# Sheet1.net
KiCad netlist of a schematic drawn in Altium Designer
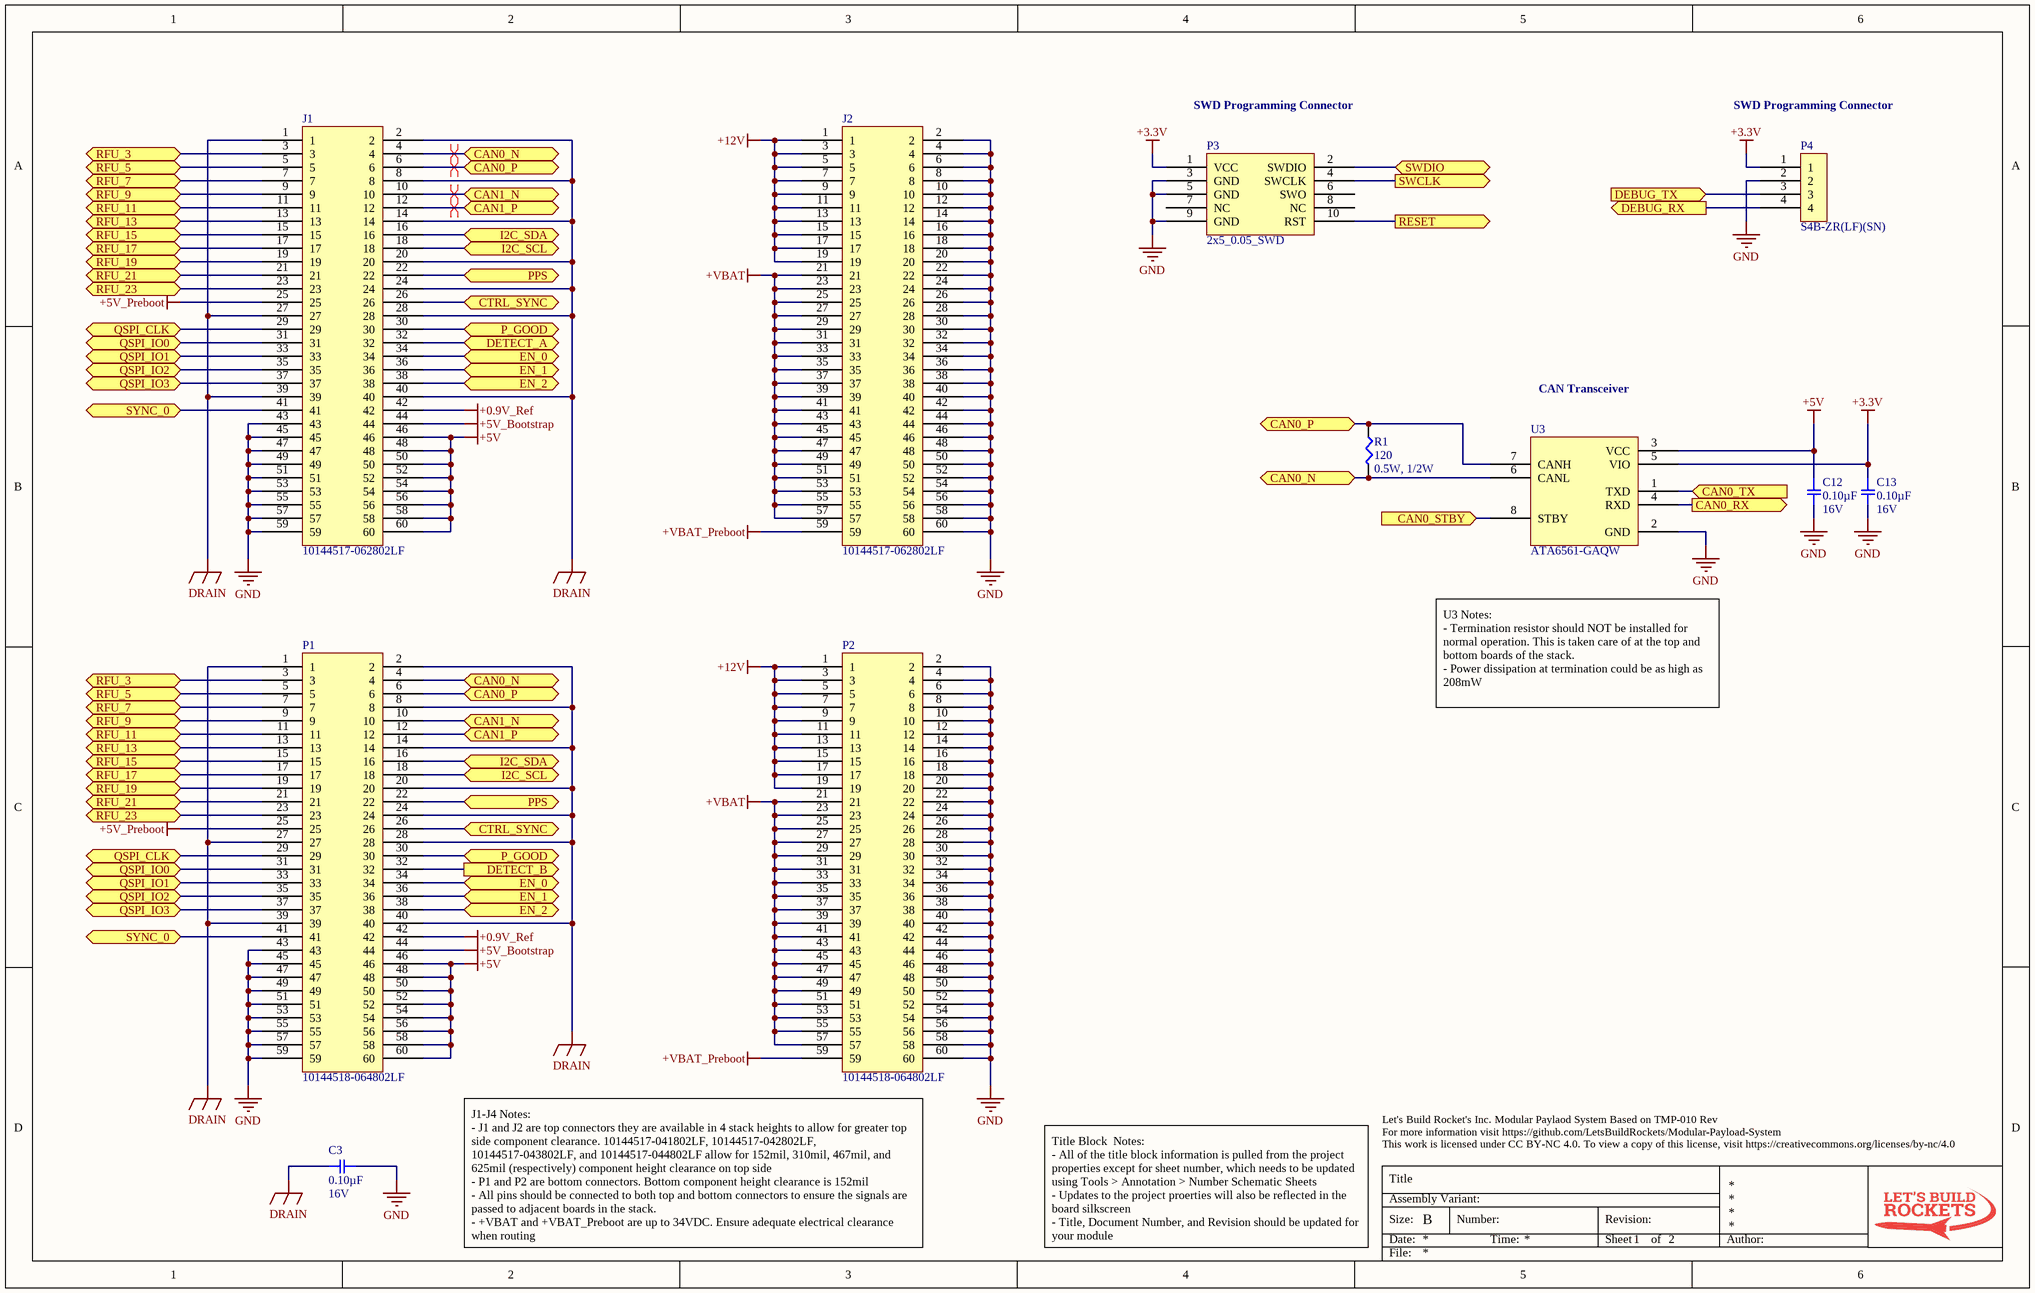
[diagram p0: Sheet1.SchDoc]

(export (version "E")
  (design (tool "Eeschema 10.0.6"))
  (components
    (comp (ref "C3")
      (value "0.10µF")
      (footprint "SMD-0402C")
      (description "CAP CER 0.1UF 16V X7R 0402")
      (fields
        (field (name "DIGI-KEY PART NUMBER") "490-4759-1-ND")
        (field (name "PART NUMBER") "GCM155R71C104KA55D")
        (field (name "VOLTAGE") "16V")
      )
      (libsource (lib "capacitor_murata_0402") (part "GCM155R71C104KA55D"))
    )
    (comp (ref "C12")
      (value "0.10µF")
      (footprint "SMD-0402C")
      (description "CAP CER 0.1UF 16V X7R 0402")
      (fields
        (field (name "DIGI-KEY PART NUMBER") "490-4759-1-ND")
        (field (name "PART NUMBER") "GCM155R71C104KA55D")
        (field (name "VOLTAGE") "16V")
      )
      (libsource (lib "capacitor_murata_0402") (part "GCM155R71C104KA55D"))
    )
    (comp (ref "C13")
      (value "0.10µF")
      (footprint "SMD-0402C")
      (description "CAP CER 0.1UF 16V X7R 0402")
      (fields
        (field (name "DIGI-KEY PART NUMBER") "490-4759-1-ND")
        (field (name "PART NUMBER") "GCM155R71C104KA55D")
        (field (name "VOLTAGE") "16V")
      )
      (libsource (lib "capacitor_murata_0402") (part "GCM155R71C104KA55D"))
    )
    (comp (ref "J1")
      (value "10144517-062802LF")
      (footprint "10144517-062802LF")
      (libsource (lib "ModularPayload") (part "10144517-062802LF"))
    )
    (comp (ref "J2")
      (value "10144517-062802LF")
      (footprint "10144517-062802LF")
      (libsource (lib "ModularPayload") (part "10144517-062802LF"))
    )
    (comp (ref "P1")
      (value "10144518-064802LF")
      (footprint "10144518-064802LF")
      (libsource (lib "ModularPayload") (part "10144518-064802LF"))
    )
    (comp (ref "P2")
      (value "10144518-064802LF")
      (footprint "10144518-064802LF")
      (libsource (lib "ModularPayload") (part "10144518-064802LF"))
    )
    (comp (ref "P3")
      (value "2x5_0.05_SWD")
      (footprint "2x5_0.05_R")
      (libsource (lib "ModularPayload") (part "2x5_0.05_SWD"))
    )
    (comp (ref "P4")
      (value "S4B-ZR(LF)(SN)")
      (footprint "S4B-ZR(LF)(SN)")
      (libsource (lib "ModularPayload") (part "S4B-ZR(LF)(SN)"))
    )
    (comp (ref "R1")
      (value "120")
      (footprint "SMD-0805-RES")
      (description "RES SMD 120 OHM 5% 1/2W 0805")
      (fields
        (field (name "PART NUMBER") "ERJ-P6WJ121V")
        (field (name "DIGI-KEY PART NUMBER") "P16943CT-ND")
        (field (name "POWER (WATTS)") "0.5W, 1/2W")
      )
      (libsource (lib "Panasonic_ERJ_0805") (part "ERJ-P6WJ121V"))
    )
    (comp (ref "U3")
      (value "ATA6561-GAQW")
      (footprint "SOIC127P600X175-8N")
      (libsource (lib "ModularPayload") (part "ATA6561-GAQW"))
    )
  )
  (nets
    (net (code "1") (name "+0.9V_Ref") (class "Default")
      (node (ref "J1") (pin "42") (pinfunction "42_42") (pintype "passive"))
      (node (ref "P1") (pin "42") (pinfunction "42_42") (pintype "passive"))
    )
    (net (code "2") (name "+3.3V") (class "Default")
      (node (ref "C13") (pin "1") (pinfunction "1_1") (pintype "passive"))
      (node (ref "P3") (pin "1") (pinfunction "VCC_1") (pintype "passive"))
      (node (ref "P4") (pin "1") (pinfunction "1_1") (pintype "passive"))
      (node (ref "U3") (pin "5") (pinfunction "VIO_5") (pintype "passive"))
    )
    (net (code "3") (name "+5V") (class "Default")
      (node (ref "C12") (pin "1") (pinfunction "1_1") (pintype "passive"))
      (node (ref "J1") (pin "46") (pinfunction "46_46") (pintype "passive"))
      (node (ref "J1") (pin "48") (pinfunction "48_48") (pintype "passive"))
      (node (ref "J1") (pin "50") (pinfunction "50_50") (pintype "passive"))
      (node (ref "J1") (pin "52") (pinfunction "52_52") (pintype "passive"))
      (node (ref "J1") (pin "54") (pinfunction "54_54") (pintype "passive"))
      (node (ref "J1") (pin "56") (pinfunction "56_56") (pintype "passive"))
      (node (ref "J1") (pin "58") (pinfunction "58_58") (pintype "passive"))
      (node (ref "J1") (pin "60") (pinfunction "60_60") (pintype "passive"))
      (node (ref "P1") (pin "46") (pinfunction "46_46") (pintype "passive"))
      (node (ref "P1") (pin "48") (pinfunction "48_48") (pintype "passive"))
      (node (ref "P1") (pin "50") (pinfunction "50_50") (pintype "passive"))
      (node (ref "P1") (pin "52") (pinfunction "52_52") (pintype "passive"))
      (node (ref "P1") (pin "54") (pinfunction "54_54") (pintype "passive"))
      (node (ref "P1") (pin "56") (pinfunction "56_56") (pintype "passive"))
      (node (ref "P1") (pin "58") (pinfunction "58_58") (pintype "passive"))
      (node (ref "P1") (pin "60") (pinfunction "60_60") (pintype "passive"))
      (node (ref "U3") (pin "3") (pinfunction "VCC_3") (pintype "passive"))
    )
    (net (code "4") (name "+5V_Bootstrap") (class "Default")
      (node (ref "J1") (pin "44") (pinfunction "44_44") (pintype "passive"))
      (node (ref "P1") (pin "44") (pinfunction "44_44") (pintype "passive"))
    )
    (net (code "5") (name "+5V_Preboot") (class "Default")
      (node (ref "J1") (pin "25") (pinfunction "25_25") (pintype "passive"))
      (node (ref "P1") (pin "25") (pinfunction "25_25") (pintype "passive"))
    )
    (net (code "6") (name "+12V") (class "Default")
      (node (ref "J2") (pin "1") (pinfunction "1_1") (pintype "passive"))
      (node (ref "J2") (pin "11") (pinfunction "11_11") (pintype "passive"))
      (node (ref "J2") (pin "13") (pinfunction "13_13") (pintype "passive"))
      (node (ref "J2") (pin "15") (pinfunction "15_15") (pintype "passive"))
      (node (ref "J2") (pin "17") (pinfunction "17_17") (pintype "passive"))
      (node (ref "J2") (pin "19") (pinfunction "19_19") (pintype "passive"))
      (node (ref "J2") (pin "3") (pinfunction "3_3") (pintype "passive"))
      (node (ref "J2") (pin "5") (pinfunction "5_5") (pintype "passive"))
      (node (ref "J2") (pin "7") (pinfunction "7_7") (pintype "passive"))
      (node (ref "J2") (pin "9") (pinfunction "9_9") (pintype "passive"))
      (node (ref "P2") (pin "1") (pinfunction "1_1") (pintype "passive"))
      (node (ref "P2") (pin "11") (pinfunction "11_11") (pintype "passive"))
      (node (ref "P2") (pin "13") (pinfunction "13_13") (pintype "passive"))
      (node (ref "P2") (pin "15") (pinfunction "15_15") (pintype "passive"))
      (node (ref "P2") (pin "17") (pinfunction "17_17") (pintype "passive"))
      (node (ref "P2") (pin "19") (pinfunction "19_19") (pintype "passive"))
      (node (ref "P2") (pin "3") (pinfunction "3_3") (pintype "passive"))
      (node (ref "P2") (pin "5") (pinfunction "5_5") (pintype "passive"))
      (node (ref "P2") (pin "7") (pinfunction "7_7") (pintype "passive"))
      (node (ref "P2") (pin "9") (pinfunction "9_9") (pintype "passive"))
    )
    (net (code "7") (name "+VBAT") (class "Default")
      (node (ref "J2") (pin "21") (pinfunction "21_21") (pintype "passive"))
      (node (ref "J2") (pin "23") (pinfunction "23_23") (pintype "passive"))
      (node (ref "J2") (pin "25") (pinfunction "25_25") (pintype "passive"))
      (node (ref "J2") (pin "27") (pinfunction "27_27") (pintype "passive"))
      (node (ref "J2") (pin "29") (pinfunction "29_29") (pintype "passive"))
      (node (ref "J2") (pin "31") (pinfunction "31_31") (pintype "passive"))
      (node (ref "J2") (pin "33") (pinfunction "33_33") (pintype "passive"))
      (node (ref "J2") (pin "35") (pinfunction "35_35") (pintype "passive"))
      (node (ref "J2") (pin "37") (pinfunction "37_37") (pintype "passive"))
      (node (ref "J2") (pin "39") (pinfunction "39_39") (pintype "passive"))
      (node (ref "J2") (pin "41") (pinfunction "41_41") (pintype "passive"))
      (node (ref "J2") (pin "43") (pinfunction "43_43") (pintype "passive"))
      (node (ref "J2") (pin "45") (pinfunction "45_45") (pintype "passive"))
      (node (ref "J2") (pin "47") (pinfunction "47_47") (pintype "passive"))
      (node (ref "J2") (pin "49") (pinfunction "49_49") (pintype "passive"))
      (node (ref "J2") (pin "51") (pinfunction "51_51") (pintype "passive"))
      (node (ref "J2") (pin "53") (pinfunction "53_53") (pintype "passive"))
      (node (ref "J2") (pin "55") (pinfunction "55_55") (pintype "passive"))
      (node (ref "J2") (pin "57") (pinfunction "57_57") (pintype "passive"))
      (node (ref "P2") (pin "21") (pinfunction "21_21") (pintype "passive"))
      (node (ref "P2") (pin "23") (pinfunction "23_23") (pintype "passive"))
      (node (ref "P2") (pin "25") (pinfunction "25_25") (pintype "passive"))
      (node (ref "P2") (pin "27") (pinfunction "27_27") (pintype "passive"))
      (node (ref "P2") (pin "29") (pinfunction "29_29") (pintype "passive"))
      (node (ref "P2") (pin "31") (pinfunction "31_31") (pintype "passive"))
      (node (ref "P2") (pin "33") (pinfunction "33_33") (pintype "passive"))
      (node (ref "P2") (pin "35") (pinfunction "35_35") (pintype "passive"))
      (node (ref "P2") (pin "37") (pinfunction "37_37") (pintype "passive"))
      (node (ref "P2") (pin "39") (pinfunction "39_39") (pintype "passive"))
      (node (ref "P2") (pin "41") (pinfunction "41_41") (pintype "passive"))
      (node (ref "P2") (pin "43") (pinfunction "43_43") (pintype "passive"))
      (node (ref "P2") (pin "45") (pinfunction "45_45") (pintype "passive"))
      (node (ref "P2") (pin "47") (pinfunction "47_47") (pintype "passive"))
      (node (ref "P2") (pin "49") (pinfunction "49_49") (pintype "passive"))
      (node (ref "P2") (pin "51") (pinfunction "51_51") (pintype "passive"))
      (node (ref "P2") (pin "53") (pinfunction "53_53") (pintype "passive"))
      (node (ref "P2") (pin "55") (pinfunction "55_55") (pintype "passive"))
      (node (ref "P2") (pin "57") (pinfunction "57_57") (pintype "passive"))
    )
    (net (code "8") (name "+VBAT_Preboot") (class "Default")
      (node (ref "J2") (pin "59") (pinfunction "59_59") (pintype "passive"))
      (node (ref "P2") (pin "59") (pinfunction "59_59") (pintype "passive"))
    )
    (net (code "9") (name "/CAN0_N") (class "Default")
      (node (ref "J1") (pin "4") (pinfunction "4_4") (pintype "passive"))
      (node (ref "P1") (pin "4") (pinfunction "4_4") (pintype "passive"))
      (node (ref "R1") (pin "2") (pinfunction "2_2") (pintype "passive"))
      (node (ref "U3") (pin "6") (pinfunction "CANL_6") (pintype "passive"))
    )
    (net (code "10") (name "/CAN0_P") (class "Default")
      (node (ref "J1") (pin "6") (pinfunction "6_6") (pintype "passive"))
      (node (ref "P1") (pin "6") (pinfunction "6_6") (pintype "passive"))
      (node (ref "R1") (pin "1") (pinfunction "1_1") (pintype "passive"))
      (node (ref "U3") (pin "7") (pinfunction "CANH_7") (pintype "passive"))
    )
    (net (code "11") (name "/CAN0_RX") (class "Default")
      (node (ref "U3") (pin "4") (pinfunction "RXD_4") (pintype "passive"))
    )
    (net (code "12") (name "/CAN0_STBY") (class "Default")
      (node (ref "U3") (pin "8") (pinfunction "STBY_8") (pintype "passive"))
    )
    (net (code "13") (name "/CAN0_TX") (class "Default")
      (node (ref "U3") (pin "1") (pinfunction "TXD_1") (pintype "passive"))
    )
    (net (code "14") (name "/CAN1_N") (class "Default")
      (node (ref "J1") (pin "10") (pinfunction "10_10") (pintype "passive"))
      (node (ref "P1") (pin "10") (pinfunction "10_10") (pintype "passive"))
    )
    (net (code "15") (name "/CAN1_P") (class "Default")
      (node (ref "J1") (pin "12") (pinfunction "12_12") (pintype "passive"))
      (node (ref "P1") (pin "12") (pinfunction "12_12") (pintype "passive"))
    )
    (net (code "16") (name "/CTRL_SYNC") (class "Default")
      (node (ref "J1") (pin "26") (pinfunction "26_26") (pintype "passive"))
      (node (ref "P1") (pin "26") (pinfunction "26_26") (pintype "passive"))
    )
    (net (code "17") (name "/DEBUG_RX") (class "Default")
      (node (ref "P4") (pin "4") (pinfunction "4_4") (pintype "passive"))
    )
    (net (code "18") (name "/DEBUG_TX") (class "Default")
      (node (ref "P4") (pin "3") (pinfunction "3_3") (pintype "passive"))
    )
    (net (code "19") (name "/DETECT_A") (class "Default")
      (node (ref "J1") (pin "32") (pinfunction "32_32") (pintype "passive"))
    )
    (net (code "20") (name "/DETECT_B") (class "Default")
      (node (ref "P1") (pin "32") (pinfunction "32_32") (pintype "passive"))
    )
    (net (code "21") (name "/EN_0") (class "Default")
      (node (ref "J1") (pin "34") (pinfunction "34_34") (pintype "passive"))
      (node (ref "P1") (pin "34") (pinfunction "34_34") (pintype "passive"))
    )
    (net (code "22") (name "/EN_1") (class "Default")
      (node (ref "J1") (pin "36") (pinfunction "36_36") (pintype "passive"))
      (node (ref "P1") (pin "36") (pinfunction "36_36") (pintype "passive"))
    )
    (net (code "23") (name "/EN_2") (class "Default")
      (node (ref "J1") (pin "38") (pinfunction "38_38") (pintype "passive"))
      (node (ref "P1") (pin "38") (pinfunction "38_38") (pintype "passive"))
    )
    (net (code "24") (name "/I2C_SCL") (class "Default")
      (node (ref "J1") (pin "18") (pinfunction "18_18") (pintype "passive"))
      (node (ref "P1") (pin "18") (pinfunction "18_18") (pintype "passive"))
    )
    (net (code "25") (name "/I2C_SDA") (class "Default")
      (node (ref "J1") (pin "16") (pinfunction "16_16") (pintype "passive"))
      (node (ref "P1") (pin "16") (pinfunction "16_16") (pintype "passive"))
    )
    (net (code "26") (name "/PPS") (class "Default")
      (node (ref "J1") (pin "22") (pinfunction "22_22") (pintype "passive"))
      (node (ref "P1") (pin "22") (pinfunction "22_22") (pintype "passive"))
    )
    (net (code "27") (name "/P_GOOD") (class "Default")
      (node (ref "J1") (pin "30") (pinfunction "30_30") (pintype "passive"))
      (node (ref "P1") (pin "30") (pinfunction "30_30") (pintype "passive"))
    )
    (net (code "28") (name "/QSPI_CLK") (class "Default")
      (node (ref "J1") (pin "29") (pinfunction "29_29") (pintype "passive"))
      (node (ref "P1") (pin "29") (pinfunction "29_29") (pintype "passive"))
    )
    (net (code "29") (name "/QSPI_IO0") (class "Default")
      (node (ref "J1") (pin "31") (pinfunction "31_31") (pintype "passive"))
      (node (ref "P1") (pin "31") (pinfunction "31_31") (pintype "passive"))
    )
    (net (code "30") (name "/QSPI_IO1") (class "Default")
      (node (ref "J1") (pin "33") (pinfunction "33_33") (pintype "passive"))
      (node (ref "P1") (pin "33") (pinfunction "33_33") (pintype "passive"))
    )
    (net (code "31") (name "/QSPI_IO2") (class "Default")
      (node (ref "J1") (pin "35") (pinfunction "35_35") (pintype "passive"))
      (node (ref "P1") (pin "35") (pinfunction "35_35") (pintype "passive"))
    )
    (net (code "32") (name "/QSPI_IO3") (class "Default")
      (node (ref "J1") (pin "37") (pinfunction "37_37") (pintype "passive"))
      (node (ref "P1") (pin "37") (pinfunction "37_37") (pintype "passive"))
    )
    (net (code "33") (name "/RESET") (class "Default")
      (node (ref "P3") (pin "10") (pinfunction "RST_10") (pintype "passive"))
    )
    (net (code "34") (name "/RFU_3") (class "Default")
      (node (ref "J1") (pin "3") (pinfunction "3_3") (pintype "passive"))
      (node (ref "P1") (pin "3") (pinfunction "3_3") (pintype "passive"))
    )
    (net (code "35") (name "/RFU_5") (class "Default")
      (node (ref "J1") (pin "5") (pinfunction "5_5") (pintype "passive"))
      (node (ref "P1") (pin "5") (pinfunction "5_5") (pintype "passive"))
    )
    (net (code "36") (name "/RFU_7") (class "Default")
      (node (ref "J1") (pin "7") (pinfunction "7_7") (pintype "passive"))
      (node (ref "P1") (pin "7") (pinfunction "7_7") (pintype "passive"))
    )
    (net (code "37") (name "/RFU_9") (class "Default")
      (node (ref "J1") (pin "9") (pinfunction "9_9") (pintype "passive"))
      (node (ref "P1") (pin "9") (pinfunction "9_9") (pintype "passive"))
    )
    (net (code "38") (name "/RFU_11") (class "Default")
      (node (ref "J1") (pin "11") (pinfunction "11_11") (pintype "passive"))
      (node (ref "P1") (pin "11") (pinfunction "11_11") (pintype "passive"))
    )
    (net (code "39") (name "/RFU_13") (class "Default")
      (node (ref "J1") (pin "13") (pinfunction "13_13") (pintype "passive"))
      (node (ref "P1") (pin "13") (pinfunction "13_13") (pintype "passive"))
    )
    (net (code "40") (name "/RFU_15") (class "Default")
      (node (ref "J1") (pin "15") (pinfunction "15_15") (pintype "passive"))
      (node (ref "P1") (pin "15") (pinfunction "15_15") (pintype "passive"))
    )
    (net (code "41") (name "/RFU_17") (class "Default")
      (node (ref "J1") (pin "17") (pinfunction "17_17") (pintype "passive"))
      (node (ref "P1") (pin "17") (pinfunction "17_17") (pintype "passive"))
    )
    (net (code "42") (name "/RFU_19") (class "Default")
      (node (ref "J1") (pin "19") (pinfunction "19_19") (pintype "passive"))
      (node (ref "P1") (pin "19") (pinfunction "19_19") (pintype "passive"))
    )
    (net (code "43") (name "/RFU_21") (class "Default")
      (node (ref "J1") (pin "21") (pinfunction "21_21") (pintype "passive"))
      (node (ref "P1") (pin "21") (pinfunction "21_21") (pintype "passive"))
    )
    (net (code "44") (name "/RFU_23") (class "Default")
      (node (ref "J1") (pin "23") (pinfunction "23_23") (pintype "passive"))
      (node (ref "P1") (pin "23") (pinfunction "23_23") (pintype "passive"))
    )
    (net (code "45") (name "/SWCLK") (class "Default")
      (node (ref "P3") (pin "4") (pinfunction "SWCLK_4") (pintype "passive"))
    )
    (net (code "46") (name "/SWDIO") (class "Default")
      (node (ref "P3") (pin "2") (pinfunction "SWDIO_2") (pintype "passive"))
    )
    (net (code "47") (name "/SYNC_0") (class "Default")
      (node (ref "J1") (pin "41") (pinfunction "41_41") (pintype "passive"))
      (node (ref "P1") (pin "41") (pinfunction "41_41") (pintype "passive"))
    )
    (net (code "48") (name "DRAIN") (class "Default")
      (node (ref "C3") (pin "2") (pinfunction "2_2") (pintype "passive"))
      (node (ref "J1") (pin "1") (pinfunction "1_1") (pintype "passive"))
      (node (ref "J1") (pin "14") (pinfunction "14_14") (pintype "passive"))
      (node (ref "J1") (pin "2") (pinfunction "2_2") (pintype "passive"))
      (node (ref "J1") (pin "20") (pinfunction "20_20") (pintype "passive"))
      (node (ref "J1") (pin "24") (pinfunction "24_24") (pintype "passive"))
      (node (ref "J1") (pin "27") (pinfunction "27_27") (pintype "passive"))
      (node (ref "J1") (pin "28") (pinfunction "28_28") (pintype "passive"))
      (node (ref "J1") (pin "39") (pinfunction "39_39") (pintype "passive"))
      (node (ref "J1") (pin "40") (pinfunction "40_40") (pintype "passive"))
      (node (ref "J1") (pin "8") (pinfunction "8_8") (pintype "passive"))
      (node (ref "P1") (pin "1") (pinfunction "1_1") (pintype "passive"))
      (node (ref "P1") (pin "14") (pinfunction "14_14") (pintype "passive"))
      (node (ref "P1") (pin "2") (pinfunction "2_2") (pintype "passive"))
      (node (ref "P1") (pin "20") (pinfunction "20_20") (pintype "passive"))
      (node (ref "P1") (pin "24") (pinfunction "24_24") (pintype "passive"))
      (node (ref "P1") (pin "27") (pinfunction "27_27") (pintype "passive"))
      (node (ref "P1") (pin "28") (pinfunction "28_28") (pintype "passive"))
      (node (ref "P1") (pin "39") (pinfunction "39_39") (pintype "passive"))
      (node (ref "P1") (pin "40") (pinfunction "40_40") (pintype "passive"))
      (node (ref "P1") (pin "8") (pinfunction "8_8") (pintype "passive"))
    )
    (net (code "49") (name "GND") (class "Default")
      (node (ref "C12") (pin "2") (pinfunction "2_2") (pintype "passive"))
      (node (ref "C13") (pin "2") (pinfunction "2_2") (pintype "passive"))
      (node (ref "C3") (pin "1") (pinfunction "1_1") (pintype "passive"))
      (node (ref "J1") (pin "43") (pinfunction "43_43") (pintype "passive"))
      (node (ref "J1") (pin "45") (pinfunction "45_45") (pintype "passive"))
      (node (ref "J1") (pin "47") (pinfunction "47_47") (pintype "passive"))
      (node (ref "J1") (pin "49") (pinfunction "49_49") (pintype "passive"))
      (node (ref "J1") (pin "51") (pinfunction "51_51") (pintype "passive"))
      (node (ref "J1") (pin "53") (pinfunction "53_53") (pintype "passive"))
      (node (ref "J1") (pin "55") (pinfunction "55_55") (pintype "passive"))
      (node (ref "J1") (pin "57") (pinfunction "57_57") (pintype "passive"))
      (node (ref "J1") (pin "59") (pinfunction "59_59") (pintype "passive"))
      (node (ref "J2") (pin "10") (pinfunction "10_10") (pintype "passive"))
      (node (ref "J2") (pin "12") (pinfunction "12_12") (pintype "passive"))
      (node (ref "J2") (pin "14") (pinfunction "14_14") (pintype "passive"))
      (node (ref "J2") (pin "16") (pinfunction "16_16") (pintype "passive"))
      (node (ref "J2") (pin "18") (pinfunction "18_18") (pintype "passive"))
      (node (ref "J2") (pin "2") (pinfunction "2_2") (pintype "passive"))
      (node (ref "J2") (pin "20") (pinfunction "20_20") (pintype "passive"))
      (node (ref "J2") (pin "22") (pinfunction "22_22") (pintype "passive"))
      (node (ref "J2") (pin "24") (pinfunction "24_24") (pintype "passive"))
      (node (ref "J2") (pin "26") (pinfunction "26_26") (pintype "passive"))
      (node (ref "J2") (pin "28") (pinfunction "28_28") (pintype "passive"))
      (node (ref "J2") (pin "30") (pinfunction "30_30") (pintype "passive"))
      (node (ref "J2") (pin "32") (pinfunction "32_32") (pintype "passive"))
      (node (ref "J2") (pin "34") (pinfunction "34_34") (pintype "passive"))
      (node (ref "J2") (pin "36") (pinfunction "36_36") (pintype "passive"))
      (node (ref "J2") (pin "38") (pinfunction "38_38") (pintype "passive"))
      (node (ref "J2") (pin "4") (pinfunction "4_4") (pintype "passive"))
      (node (ref "J2") (pin "40") (pinfunction "40_40") (pintype "passive"))
      (node (ref "J2") (pin "42") (pinfunction "42_42") (pintype "passive"))
      (node (ref "J2") (pin "44") (pinfunction "44_44") (pintype "passive"))
      (node (ref "J2") (pin "46") (pinfunction "46_46") (pintype "passive"))
      (node (ref "J2") (pin "48") (pinfunction "48_48") (pintype "passive"))
      (node (ref "J2") (pin "50") (pinfunction "50_50") (pintype "passive"))
      (node (ref "J2") (pin "52") (pinfunction "52_52") (pintype "passive"))
      (node (ref "J2") (pin "54") (pinfunction "54_54") (pintype "passive"))
      (node (ref "J2") (pin "56") (pinfunction "56_56") (pintype "passive"))
      (node (ref "J2") (pin "58") (pinfunction "58_58") (pintype "passive"))
      (node (ref "J2") (pin "6") (pinfunction "6_6") (pintype "passive"))
      (node (ref "J2") (pin "60") (pinfunction "60_60") (pintype "passive"))
      (node (ref "J2") (pin "8") (pinfunction "8_8") (pintype "passive"))
      (node (ref "P1") (pin "43") (pinfunction "43_43") (pintype "passive"))
      (node (ref "P1") (pin "45") (pinfunction "45_45") (pintype "passive"))
      (node (ref "P1") (pin "47") (pinfunction "47_47") (pintype "passive"))
      (node (ref "P1") (pin "49") (pinfunction "49_49") (pintype "passive"))
      (node (ref "P1") (pin "51") (pinfunction "51_51") (pintype "passive"))
      (node (ref "P1") (pin "53") (pinfunction "53_53") (pintype "passive"))
      (node (ref "P1") (pin "55") (pinfunction "55_55") (pintype "passive"))
      (node (ref "P1") (pin "57") (pinfunction "57_57") (pintype "passive"))
      (node (ref "P1") (pin "59") (pinfunction "59_59") (pintype "passive"))
      (node (ref "P2") (pin "10") (pinfunction "10_10") (pintype "passive"))
      (node (ref "P2") (pin "12") (pinfunction "12_12") (pintype "passive"))
      (node (ref "P2") (pin "14") (pinfunction "14_14") (pintype "passive"))
      (node (ref "P2") (pin "16") (pinfunction "16_16") (pintype "passive"))
      (node (ref "P2") (pin "18") (pinfunction "18_18") (pintype "passive"))
      (node (ref "P2") (pin "2") (pinfunction "2_2") (pintype "passive"))
      (node (ref "P2") (pin "20") (pinfunction "20_20") (pintype "passive"))
      (node (ref "P2") (pin "22") (pinfunction "22_22") (pintype "passive"))
      (node (ref "P2") (pin "24") (pinfunction "24_24") (pintype "passive"))
      (node (ref "P2") (pin "26") (pinfunction "26_26") (pintype "passive"))
      (node (ref "P2") (pin "28") (pinfunction "28_28") (pintype "passive"))
      (node (ref "P2") (pin "30") (pinfunction "30_30") (pintype "passive"))
      (node (ref "P2") (pin "32") (pinfunction "32_32") (pintype "passive"))
      (node (ref "P2") (pin "34") (pinfunction "34_34") (pintype "passive"))
      (node (ref "P2") (pin "36") (pinfunction "36_36") (pintype "passive"))
      (node (ref "P2") (pin "38") (pinfunction "38_38") (pintype "passive"))
      (node (ref "P2") (pin "4") (pinfunction "4_4") (pintype "passive"))
      (node (ref "P2") (pin "40") (pinfunction "40_40") (pintype "passive"))
      (node (ref "P2") (pin "42") (pinfunction "42_42") (pintype "passive"))
      (node (ref "P2") (pin "44") (pinfunction "44_44") (pintype "passive"))
      (node (ref "P2") (pin "46") (pinfunction "46_46") (pintype "passive"))
      (node (ref "P2") (pin "48") (pinfunction "48_48") (pintype "passive"))
      (node (ref "P2") (pin "50") (pinfunction "50_50") (pintype "passive"))
      (node (ref "P2") (pin "52") (pinfunction "52_52") (pintype "passive"))
      (node (ref "P2") (pin "54") (pinfunction "54_54") (pintype "passive"))
      (node (ref "P2") (pin "56") (pinfunction "56_56") (pintype "passive"))
      (node (ref "P2") (pin "58") (pinfunction "58_58") (pintype "passive"))
      (node (ref "P2") (pin "6") (pinfunction "6_6") (pintype "passive"))
      (node (ref "P2") (pin "60") (pinfunction "60_60") (pintype "passive"))
      (node (ref "P2") (pin "8") (pinfunction "8_8") (pintype "passive"))
      (node (ref "P3") (pin "3") (pinfunction "GND_3") (pintype "passive"))
      (node (ref "P3") (pin "5") (pinfunction "GND_5") (pintype "passive"))
      (node (ref "P3") (pin "9") (pinfunction "GND_9") (pintype "passive"))
      (node (ref "P4") (pin "2") (pinfunction "2_2") (pintype "passive"))
      (node (ref "U3") (pin "2") (pinfunction "GND_2") (pintype "passive"))
    )
    (net (code "50") (name "unconnected-(P3-NC-Pad7)") (class "Default")
      (node (ref "P3") (pin "7") (pinfunction "NC_7") (pintype "passive"))
    )
    (net (code "51") (name "unconnected-(P3-NC-Pad8)") (class "Default")
      (node (ref "P3") (pin "8") (pinfunction "NC_8") (pintype "passive"))
    )
    (net (code "52") (name "unconnected-(P3-SWO-Pad6)") (class "Default")
      (node (ref "P3") (pin "6") (pinfunction "SWO_6") (pintype "passive"))
    )
  )
)
